# conc_contro0l.net
KiCad netlist of a schematic drawn in EAGLE
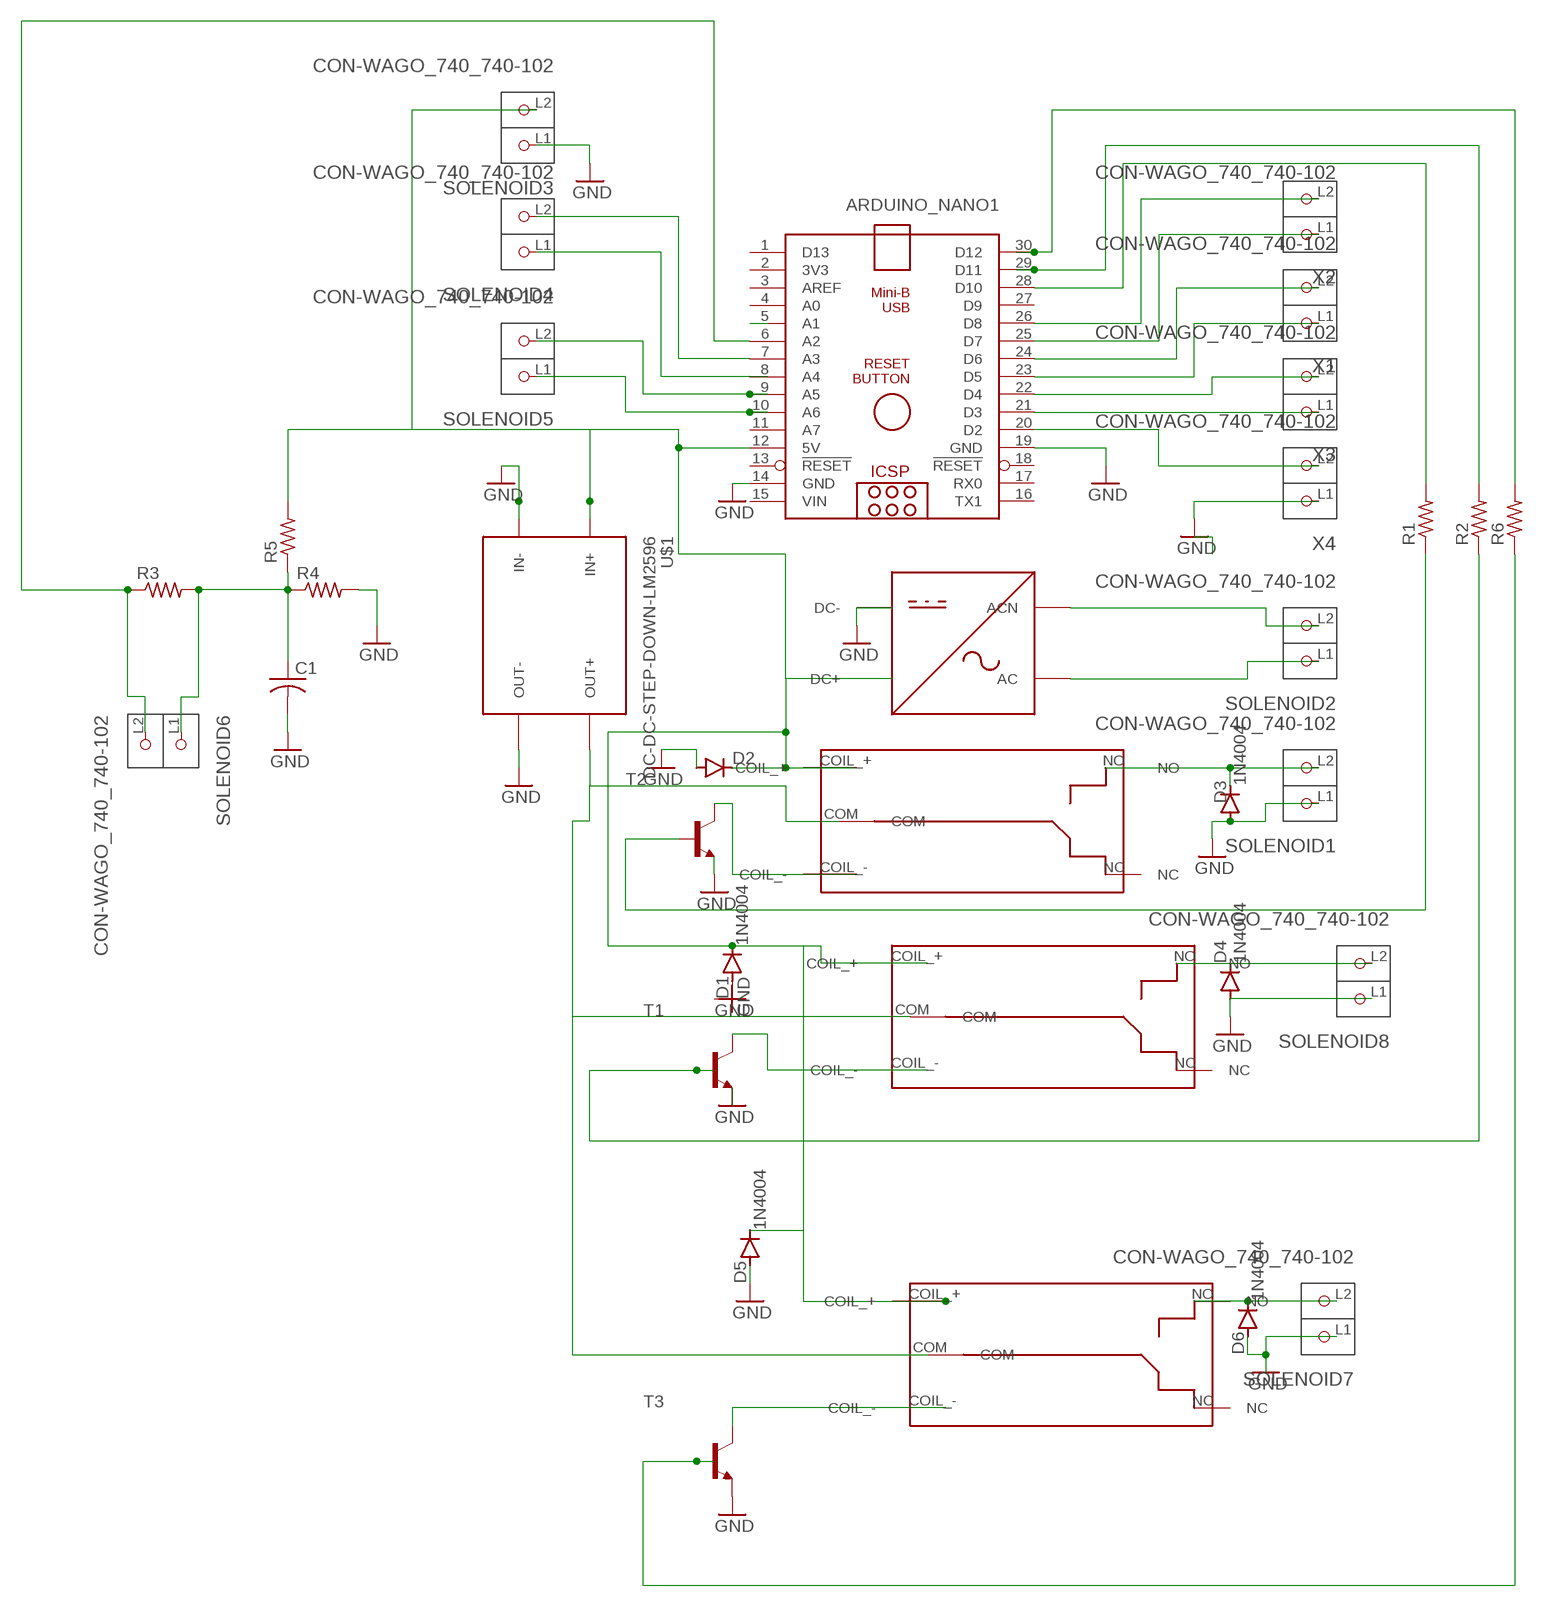
[diagram p0: schematic, sheet 1]

(export (version "E")
  (design (tool "Eeschema 10.0.6"))
  (components
    (comp (ref "ACDC")
      (value "RPD10W1S")
      (footprint "eagle-import:2343")
      (libsource (lib "eagle-import") (part "RPD10W1S"))
    )
    (comp (ref "ARDUINO_NANO1")
      (value "ARDUINONANOV30-GHIT_ARDUINO_NANO")
      (footprint "eagle-import:ARDUINONANOV30-GHIT_ARDUINO_NANO")
      (libsource (lib "eagle-import") (part "ARDUINONANOV30-GHIT_ARDUINO_NANO"))
    )
    (comp (ref "C1")
      (value "C-US025-024X044")
      (footprint "eagle-import:C025-024X044")
      (libsource (lib "eagle-import") (part "C-US025-024X044"))
    )
    (comp (ref "D1")
      (value "1N4004")
      (footprint "eagle-import:DO41-10")
      (libsource (lib "eagle-import") (part "1N4004"))
    )
    (comp (ref "D2")
      (value "1N4004")
      (footprint "eagle-import:DO41-10")
      (libsource (lib "eagle-import") (part "1N4004"))
    )
    (comp (ref "D3")
      (value "1N4004")
      (footprint "eagle-import:DO41-10")
      (libsource (lib "eagle-import") (part "1N4004"))
    )
    (comp (ref "D4")
      (value "1N4004")
      (footprint "eagle-import:DO41-10")
      (libsource (lib "eagle-import") (part "1N4004"))
    )
    (comp (ref "D5")
      (value "1N4004")
      (footprint "eagle-import:DO41-10")
      (libsource (lib "eagle-import") (part "1N4004"))
    )
    (comp (ref "D6")
      (value "1N4004")
      (footprint "eagle-import:DO41-10")
      (libsource (lib "eagle-import") (part "1N4004"))
    )
    (comp (ref "R1")
      (value "R-US_0411/15")
      (footprint "eagle-import:0411_15")
      (libsource (lib "eagle-import") (part "R-US_0411/15"))
    )
    (comp (ref "R2")
      (value "R-US_0411/15")
      (footprint "eagle-import:0411_15")
      (libsource (lib "eagle-import") (part "R-US_0411/15"))
    )
    (comp (ref "R3")
      (value "R-US_0309/10")
      (footprint "eagle-import:0309_10")
      (libsource (lib "eagle-import") (part "R-US_0309/10"))
    )
    (comp (ref "R4")
      (value "R-US_0309/10")
      (footprint "eagle-import:0309_10")
      (libsource (lib "eagle-import") (part "R-US_0309/10"))
    )
    (comp (ref "R5")
      (value "R-US_0309/10")
      (footprint "eagle-import:0309_10")
      (libsource (lib "eagle-import") (part "R-US_0309/10"))
    )
    (comp (ref "R6")
      (value "R-US_0411/15")
      (footprint "eagle-import:0411_15")
      (libsource (lib "eagle-import") (part "R-US_0411/15"))
    )
    (comp (ref "SOLENOID1")
      (value "CON-WAGO_740_740-102")
      (footprint "eagle-import:CON-WAGO_740_P-740-102")
      (libsource (lib "eagle-import") (part "CON-WAGO_740_740-102"))
    )
    (comp (ref "SOLENOID2")
      (value "CON-WAGO_740_740-102")
      (footprint "eagle-import:CON-WAGO_740_P-740-102")
      (libsource (lib "eagle-import") (part "CON-WAGO_740_740-102"))
    )
    (comp (ref "SOLENOID3")
      (value "CON-WAGO_740_740-102")
      (footprint "eagle-import:CON-WAGO_740_P-740-102")
      (libsource (lib "eagle-import") (part "CON-WAGO_740_740-102"))
    )
    (comp (ref "SOLENOID4")
      (value "CON-WAGO_740_740-102")
      (footprint "eagle-import:CON-WAGO_740_P-740-102")
      (libsource (lib "eagle-import") (part "CON-WAGO_740_740-102"))
    )
    (comp (ref "SOLENOID5")
      (value "CON-WAGO_740_740-102")
      (footprint "eagle-import:CON-WAGO_740_P-740-102")
      (libsource (lib "eagle-import") (part "CON-WAGO_740_740-102"))
    )
    (comp (ref "SOLENOID6")
      (value "CON-WAGO_740_740-102")
      (footprint "eagle-import:CON-WAGO_740_P-740-102")
      (libsource (lib "eagle-import") (part "CON-WAGO_740_740-102"))
    )
    (comp (ref "SOLENOID7")
      (value "CON-WAGO_740_740-102")
      (footprint "eagle-import:CON-WAGO_740_P-740-102")
      (libsource (lib "eagle-import") (part "CON-WAGO_740_740-102"))
    )
    (comp (ref "SOLENOID8")
      (value "CON-WAGO_740_740-102")
      (footprint "eagle-import:CON-WAGO_740_P-740-102")
      (libsource (lib "eagle-import") (part "CON-WAGO_740_740-102"))
    )
    (comp (ref "T1")
      (value "2N2222-NPN-TO92-EBC")
      (footprint "eagle-import:TO92-EBC")
      (libsource (lib "eagle-import") (part "-NPN-TO92-EBC2N2222"))
    )
    (comp (ref "T2")
      (value "2N2222-NPN-TO92-EBC")
      (footprint "eagle-import:TO92-EBC")
      (libsource (lib "eagle-import") (part "-NPN-TO92-EBC2N2222"))
    )
    (comp (ref "T3")
      (value "2N2222-NPN-TO92-EBC")
      (footprint "eagle-import:TO92-EBC")
      (libsource (lib "eagle-import") (part "-NPN-TO92-EBC2N2222"))
    )
    (comp (ref "U$1")
      (value "DC-DC-STEP-DOWN-LM2596")
      (footprint "eagle-import:DC-DC-STEP-DOWN-LM2596")
      (libsource (lib "eagle-import") (part "DC-DC-STEP-DOWN-LM2596"))
    )
    (comp (ref "U$2")
      (value "RELAY_JQC-3F(T73)A")
      (footprint "eagle-import:JQC-3F(T73)")
      (libsource (lib "eagle-import") (part "RELAY_JQC-3F(T73)A"))
    )
    (comp (ref "U$3")
      (value "RELAY_JQC-3F(T73)A")
      (footprint "eagle-import:JQC-3F(T73)")
      (libsource (lib "eagle-import") (part "RELAY_JQC-3F(T73)A"))
    )
    (comp (ref "U$4")
      (value "RELAY_JQC-3F(T73)A")
      (footprint "eagle-import:JQC-3F(T73)")
      (libsource (lib "eagle-import") (part "RELAY_JQC-3F(T73)A"))
    )
    (comp (ref "X1")
      (value "CON-WAGO_740_740-102")
      (footprint "eagle-import:CON-WAGO_740_P-740-102")
      (libsource (lib "eagle-import") (part "CON-WAGO_740_740-102"))
    )
    (comp (ref "X2")
      (value "CON-WAGO_740_740-102")
      (footprint "eagle-import:CON-WAGO_740_P-740-102")
      (libsource (lib "eagle-import") (part "CON-WAGO_740_740-102"))
    )
    (comp (ref "X3")
      (value "CON-WAGO_740_740-102")
      (footprint "eagle-import:CON-WAGO_740_P-740-102")
      (libsource (lib "eagle-import") (part "CON-WAGO_740_740-102"))
    )
    (comp (ref "X4")
      (value "CON-WAGO_740_740-102")
      (footprint "eagle-import:CON-WAGO_740_P-740-102")
      (libsource (lib "eagle-import") (part "CON-WAGO_740_740-102"))
    )
  )
  (nets
    (net (code "1") (name "/VIN") (class "Default")
      (node (ref "ARDUINO_NANO1") (pin "15") (pinfunction "VIN_15") (pintype "power_in"))
    )
    (net (code "2") (name "GND") (class "Default")
      (node (ref "ACDC") (pin "DC-") (pinfunction "DC-_DC-") (pintype "bidirectional"))
      (node (ref "ARDUINO_NANO1") (pin "14") (pinfunction "GND_14") (pintype "power_in"))
      (node (ref "ARDUINO_NANO1") (pin "19") (pinfunction "GND_19") (pintype "power_in"))
      (node (ref "C1") (pin "2") (pinfunction "2_2") (pintype "passive"))
      (node (ref "D1") (pin "A") (pinfunction "A_A") (pintype "passive"))
      (node (ref "D2") (pin "A") (pinfunction "A_A") (pintype "passive"))
      (node (ref "D3") (pin "A") (pinfunction "A_A") (pintype "passive"))
      (node (ref "D4") (pin "A") (pinfunction "A_A") (pintype "passive"))
      (node (ref "D5") (pin "A") (pinfunction "A_A") (pintype "passive"))
      (node (ref "D6") (pin "A") (pinfunction "A_A") (pintype "passive"))
      (node (ref "R4") (pin "2") (pinfunction "2_2") (pintype "passive"))
      (node (ref "SOLENOID1") (pin "L1") (pinfunction "P1_L1") (pintype "bidirectional"))
      (node (ref "SOLENOID3") (pin "L1") (pinfunction "P1_L1") (pintype "bidirectional"))
      (node (ref "SOLENOID7") (pin "L1") (pinfunction "P1_L1") (pintype "bidirectional"))
      (node (ref "SOLENOID8") (pin "L1") (pinfunction "P1_L1") (pintype "bidirectional"))
      (node (ref "T1") (pin "E") (pinfunction "E_E") (pintype "passive"))
      (node (ref "T2") (pin "E") (pinfunction "E_E") (pintype "passive"))
      (node (ref "T3") (pin "E") (pinfunction "E_E") (pintype "passive"))
      (node (ref "U$1") (pin "IN-") (pinfunction "IN-_IN-") (pintype "bidirectional"))
      (node (ref "U$1") (pin "OUT-") (pinfunction "OUT-_OUT-") (pintype "bidirectional"))
      (node (ref "X4") (pin "L1") (pinfunction "P1_L1") (pintype "bidirectional"))
    )
    (net (code "3") (name "Net-(ARDUINO_NANO1-5V)") (class "Default")
      (node (ref "ACDC") (pin "DC+") (pinfunction "DC+_DC+") (pintype "bidirectional"))
      (node (ref "ARDUINO_NANO1") (pin "12") (pinfunction "5V_12") (pintype "power_in"))
      (node (ref "D1") (pin "C") (pinfunction "C_C") (pintype "passive"))
      (node (ref "D2") (pin "C") (pinfunction "C_C") (pintype "passive"))
      (node (ref "D5") (pin "C") (pinfunction "C_C") (pintype "passive"))
      (node (ref "R5") (pin "2") (pinfunction "2_2") (pintype "passive"))
      (node (ref "SOLENOID3") (pin "L2") (pinfunction "P2_L2") (pintype "bidirectional"))
      (node (ref "U$1") (pin "IN+") (pinfunction "IN+_IN+") (pintype "bidirectional"))
      (node (ref "U$2") (pin "COIL_+") (pinfunction "COIL_+_COIL_+") (pintype "bidirectional"))
      (node (ref "U$3") (pin "COIL_+") (pinfunction "COIL_+_COIL_+") (pintype "bidirectional"))
      (node (ref "U$4") (pin "COIL_+") (pinfunction "COIL_+_COIL_+") (pintype "bidirectional"))
    )
    (net (code "4") (name "Net-(ARDUINO_NANO1-A2)") (class "Default")
      (node (ref "ARDUINO_NANO1") (pin "6") (pinfunction "A2_6") (pintype "bidirectional"))
      (node (ref "R3") (pin "1") (pinfunction "1_1") (pintype "passive"))
      (node (ref "SOLENOID6") (pin "L2") (pinfunction "P2_L2") (pintype "bidirectional"))
    )
    (net (code "5") (name "Net-(ARDUINO_NANO1-A3)") (class "Default")
      (node (ref "ARDUINO_NANO1") (pin "7") (pinfunction "A3_7") (pintype "bidirectional"))
      (node (ref "SOLENOID4") (pin "L2") (pinfunction "P2_L2") (pintype "bidirectional"))
    )
    (net (code "6") (name "Net-(ARDUINO_NANO1-A4)") (class "Default")
      (node (ref "ARDUINO_NANO1") (pin "8") (pinfunction "A4_8") (pintype "bidirectional"))
      (node (ref "SOLENOID4") (pin "L1") (pinfunction "P1_L1") (pintype "bidirectional"))
    )
    (net (code "7") (name "Net-(ARDUINO_NANO1-A5)") (class "Default")
      (node (ref "ARDUINO_NANO1") (pin "9") (pinfunction "A5_9") (pintype "bidirectional"))
      (node (ref "SOLENOID5") (pin "L2") (pinfunction "P2_L2") (pintype "bidirectional"))
    )
    (net (code "8") (name "Net-(ARDUINO_NANO1-A6)") (class "Default")
      (node (ref "ARDUINO_NANO1") (pin "10") (pinfunction "A6_10") (pintype "bidirectional"))
      (node (ref "SOLENOID5") (pin "L1") (pinfunction "P1_L1") (pintype "bidirectional"))
    )
    (net (code "9") (name "Net-(ARDUINO_NANO1-D2)") (class "Default")
      (node (ref "ARDUINO_NANO1") (pin "20") (pinfunction "D2_20") (pintype "bidirectional"))
      (node (ref "X4") (pin "L2") (pinfunction "P2_L2") (pintype "bidirectional"))
    )
    (net (code "10") (name "Net-(ARDUINO_NANO1-D3)") (class "Default")
      (node (ref "ARDUINO_NANO1") (pin "21") (pinfunction "D3_21") (pintype "bidirectional"))
      (node (ref "X3") (pin "L1") (pinfunction "P1_L1") (pintype "bidirectional"))
    )
    (net (code "11") (name "Net-(ARDUINO_NANO1-D4)") (class "Default")
      (node (ref "ARDUINO_NANO1") (pin "22") (pinfunction "D4_22") (pintype "bidirectional"))
      (node (ref "X3") (pin "L2") (pinfunction "P2_L2") (pintype "bidirectional"))
    )
    (net (code "12") (name "Net-(ARDUINO_NANO1-D5)") (class "Default")
      (node (ref "ARDUINO_NANO1") (pin "23") (pinfunction "D5_23") (pintype "bidirectional"))
      (node (ref "X1") (pin "L1") (pinfunction "P1_L1") (pintype "bidirectional"))
    )
    (net (code "13") (name "Net-(ARDUINO_NANO1-D6)") (class "Default")
      (node (ref "ARDUINO_NANO1") (pin "24") (pinfunction "D6_24") (pintype "bidirectional"))
      (node (ref "X1") (pin "L2") (pinfunction "P2_L2") (pintype "bidirectional"))
    )
    (net (code "14") (name "Net-(ARDUINO_NANO1-D7)") (class "Default")
      (node (ref "ARDUINO_NANO1") (pin "25") (pinfunction "D7_25") (pintype "bidirectional"))
      (node (ref "X2") (pin "L1") (pinfunction "P1_L1") (pintype "bidirectional"))
    )
    (net (code "15") (name "Net-(ARDUINO_NANO1-D8)") (class "Default")
      (node (ref "ARDUINO_NANO1") (pin "26") (pinfunction "D8_26") (pintype "bidirectional"))
      (node (ref "X2") (pin "L2") (pinfunction "P2_L2") (pintype "bidirectional"))
    )
    (net (code "16") (name "Net-(ARDUINO_NANO1-D10)") (class "Default")
      (node (ref "ARDUINO_NANO1") (pin "28") (pinfunction "D10_28") (pintype "bidirectional"))
      (node (ref "R1") (pin "2") (pinfunction "2_2") (pintype "passive"))
    )
    (net (code "17") (name "Net-(ARDUINO_NANO1-D11)") (class "Default")
      (node (ref "ARDUINO_NANO1") (pin "29") (pinfunction "D11_29") (pintype "bidirectional"))
      (node (ref "R2") (pin "2") (pinfunction "2_2") (pintype "passive"))
    )
    (net (code "18") (name "Net-(ARDUINO_NANO1-D12)") (class "Default")
      (node (ref "ARDUINO_NANO1") (pin "30") (pinfunction "D12_30") (pintype "bidirectional"))
      (node (ref "R6") (pin "2") (pinfunction "2_2") (pintype "passive"))
    )
    (net (code "19") (name "Net-(R1-Pad1)") (class "Default")
      (node (ref "R1") (pin "1") (pinfunction "1_1") (pintype "passive"))
      (node (ref "T2") (pin "B") (pinfunction "B_B") (pintype "passive"))
    )
    (net (code "20") (name "Net-(R2-Pad1)") (class "Default")
      (node (ref "R2") (pin "1") (pinfunction "1_1") (pintype "passive"))
      (node (ref "T1") (pin "B") (pinfunction "B_B") (pintype "passive"))
    )
    (net (code "21") (name "Net-(R6-Pad1)") (class "Default")
      (node (ref "R6") (pin "1") (pinfunction "1_1") (pintype "passive"))
      (node (ref "T3") (pin "B") (pinfunction "B_B") (pintype "passive"))
    )
    (net (code "22") (name "Net-(SOLENOID1-P2)") (class "Default")
      (node (ref "D3") (pin "C") (pinfunction "C_C") (pintype "passive"))
      (node (ref "SOLENOID1") (pin "L2") (pinfunction "P2_L2") (pintype "bidirectional"))
      (node (ref "U$2") (pin "NO") (pinfunction "NO_NO") (pintype "bidirectional"))
    )
    (net (code "23") (name "Net-(SOLENOID2-P1)") (class "Default")
      (node (ref "ACDC") (pin "AC") (pinfunction "AC_AC") (pintype "bidirectional"))
      (node (ref "SOLENOID2") (pin "L1") (pinfunction "P1_L1") (pintype "bidirectional"))
    )
    (net (code "24") (name "Net-(SOLENOID2-P2)") (class "Default")
      (node (ref "ACDC") (pin "ACN") (pinfunction "ACN_ACN") (pintype "bidirectional"))
      (node (ref "SOLENOID2") (pin "L2") (pinfunction "P2_L2") (pintype "bidirectional"))
    )
    (net (code "25") (name "Net-(SOLENOID6-P1)") (class "Default")
      (node (ref "C1") (pin "1") (pinfunction "1_1") (pintype "passive"))
      (node (ref "R3") (pin "2") (pinfunction "2_2") (pintype "passive"))
      (node (ref "R4") (pin "1") (pinfunction "1_1") (pintype "passive"))
      (node (ref "R5") (pin "1") (pinfunction "1_1") (pintype "passive"))
      (node (ref "SOLENOID6") (pin "L1") (pinfunction "P1_L1") (pintype "bidirectional"))
    )
    (net (code "26") (name "Net-(SOLENOID7-P2)") (class "Default")
      (node (ref "D6") (pin "C") (pinfunction "C_C") (pintype "passive"))
      (node (ref "SOLENOID7") (pin "L2") (pinfunction "P2_L2") (pintype "bidirectional"))
      (node (ref "U$4") (pin "NO") (pinfunction "NO_NO") (pintype "bidirectional"))
    )
    (net (code "27") (name "Net-(SOLENOID8-P2)") (class "Default")
      (node (ref "D4") (pin "C") (pinfunction "C_C") (pintype "passive"))
      (node (ref "SOLENOID8") (pin "L2") (pinfunction "P2_L2") (pintype "bidirectional"))
      (node (ref "U$3") (pin "NO") (pinfunction "NO_NO") (pintype "bidirectional"))
    )
    (net (code "28") (name "Net-(T1-PadC)") (class "Default")
      (node (ref "T1") (pin "C") (pinfunction "C_C") (pintype "passive"))
      (node (ref "U$3") (pin "COIL_-") (pinfunction "COIL_-_COIL_-") (pintype "bidirectional"))
    )
    (net (code "29") (name "Net-(T2-PadC)") (class "Default")
      (node (ref "T2") (pin "C") (pinfunction "C_C") (pintype "passive"))
      (node (ref "U$2") (pin "COIL_-") (pinfunction "COIL_-_COIL_-") (pintype "bidirectional"))
    )
    (net (code "30") (name "Net-(T3-PadC)") (class "Default")
      (node (ref "T3") (pin "C") (pinfunction "C_C") (pintype "passive"))
      (node (ref "U$4") (pin "COIL_-") (pinfunction "COIL_-_COIL_-") (pintype "bidirectional"))
    )
    (net (code "31") (name "Net-(U$1-PadOUT+)") (class "Default")
      (node (ref "U$1") (pin "OUT+") (pinfunction "OUT+_OUT+") (pintype "bidirectional"))
      (node (ref "U$2") (pin "COM") (pinfunction "COM_COM") (pintype "bidirectional"))
      (node (ref "U$3") (pin "COM") (pinfunction "COM_COM") (pintype "bidirectional"))
      (node (ref "U$4") (pin "COM") (pinfunction "COM_COM") (pintype "bidirectional"))
    )
    (net (code "32") (name "unconnected-(ARDUINO_NANO1-3V3-Pad2)") (class "Default")
      (node (ref "ARDUINO_NANO1") (pin "2") (pinfunction "3V3_2") (pintype "output"))
    )
    (net (code "33") (name "unconnected-(ARDUINO_NANO1-A0-Pad4)") (class "Default")
      (node (ref "ARDUINO_NANO1") (pin "4") (pinfunction "A0_4") (pintype "bidirectional"))
    )
    (net (code "34") (name "unconnected-(ARDUINO_NANO1-A1-Pad5)") (class "Default")
      (node (ref "ARDUINO_NANO1") (pin "5") (pinfunction "A1_5") (pintype "bidirectional"))
    )
    (net (code "35") (name "unconnected-(ARDUINO_NANO1-A7-Pad11)") (class "Default")
      (node (ref "ARDUINO_NANO1") (pin "11") (pinfunction "A7_11") (pintype "bidirectional"))
    )
    (net (code "36") (name "unconnected-(ARDUINO_NANO1-AREF-Pad3)") (class "Default")
      (node (ref "ARDUINO_NANO1") (pin "3") (pinfunction "AREF_3") (pintype "input"))
    )
    (net (code "37") (name "unconnected-(ARDUINO_NANO1-D9-Pad27)") (class "Default")
      (node (ref "ARDUINO_NANO1") (pin "27") (pinfunction "D9_27") (pintype "bidirectional"))
    )
    (net (code "38") (name "unconnected-(ARDUINO_NANO1-D13-Pad1)") (class "Default")
      (node (ref "ARDUINO_NANO1") (pin "1") (pinfunction "D13_1") (pintype "bidirectional"))
    )
    (net (code "39") (name "unconnected-(ARDUINO_NANO1-RX0-Pad17)") (class "Default")
      (node (ref "ARDUINO_NANO1") (pin "17") (pinfunction "RX0_17") (pintype "bidirectional"))
    )
    (net (code "40") (name "unconnected-(ARDUINO_NANO1-TX1-Pad16)") (class "Default")
      (node (ref "ARDUINO_NANO1") (pin "16") (pinfunction "TX1_16") (pintype "bidirectional"))
    )
    (net (code "41") (name "unconnected-(ARDUINO_NANO1-~{RESET}-Pad13)") (class "Default")
      (node (ref "ARDUINO_NANO1") (pin "13") (pinfunction "~{RESET}_13") (pintype "input"))
    )
    (net (code "42") (name "unconnected-(ARDUINO_NANO1-~{RESET}-Pad18)") (class "Default")
      (node (ref "ARDUINO_NANO1") (pin "18") (pinfunction "~{RESET}_18") (pintype "input"))
    )
    (net (code "43") (name "unconnected-(U$2-PadNC)") (class "Default")
      (node (ref "U$2") (pin "NC") (pinfunction "NC_NC") (pintype "bidirectional"))
    )
    (net (code "44") (name "unconnected-(U$3-PadNC)") (class "Default")
      (node (ref "U$3") (pin "NC") (pinfunction "NC_NC") (pintype "bidirectional"))
    )
    (net (code "45") (name "unconnected-(U$4-PadNC)") (class "Default")
      (node (ref "U$4") (pin "NC") (pinfunction "NC_NC") (pintype "bidirectional"))
    )
  )
)
